# FPGA_IO.net
KiCad netlist of a schematic drawn in Altium Designer
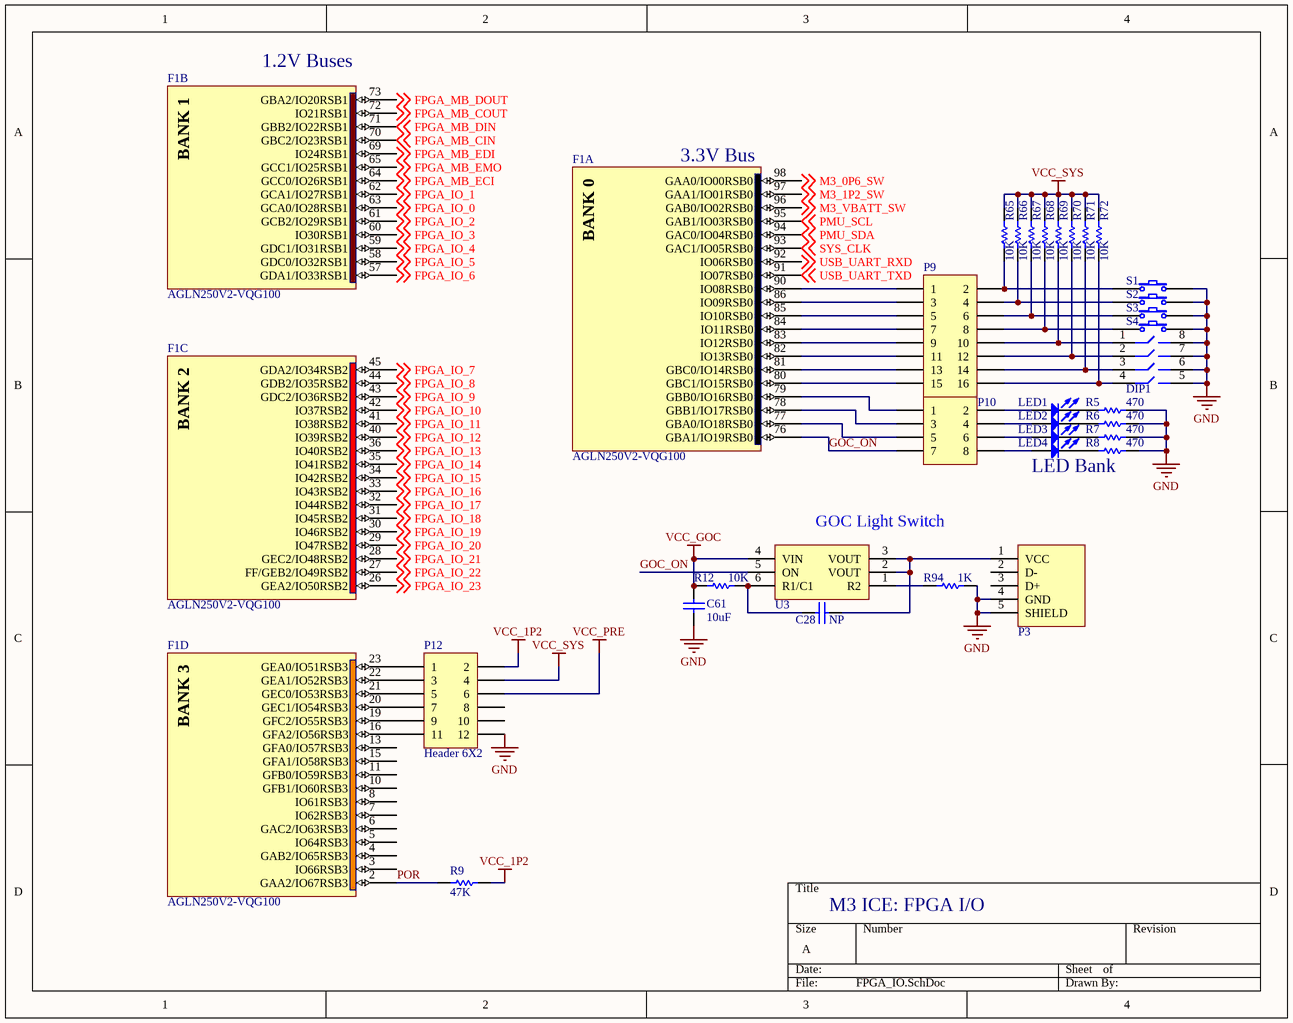
[diagram p0: FPGA_IO.SchDoc]

(export (version "E")
  (design (tool "Eeschema 10.0.6"))
  (components
    (comp (ref "C28")
      (value "NP")
      (footprint "0402")
      (description "Capacitor (Semiconductor SIM Model)")
      (fields (field (name "Comment") "Cap Semi") (field (name "PUBLISHER") "Altium Limited"))
      (libsource (lib "Miscellaneous Devices") (part "Cap Semi"))
    )
    (comp (ref "C61")
      (value "10uF")
      (footprint "0805")
      (description "Capacitor (Semiconductor SIM Model)")
      (fields
        (field (name "DISTPARTNO") "445-6857-1-ND")
        (field (name "MANPARTNO") "C2012X7R1A106K")
        (field (name "PUBLISHER") "Altium Limited")
      )
      (libsource (lib "M3") (part "Cap Chip"))
    )
    (comp (ref "DIP1")
      (value "ADE0404")
      (footprint "DIP-8")
      (description "4-DIP Switch")
      (fields (field (name "DISTPARTNO") "450-1364-ND"))
      (libsource (lib "M3") (part "ADE0404"))
    )
    (comp (ref "F1")
      (value "AGLN250V2-VQG100")
      (footprint "VQ100_N")
      (fields (field (name "DISTPARTNO") "1100-1134-ND") (field (name "PUBLISHER") "Altium Limited"))
      (libsource (lib "Actel IGLOO nano") (part "AGLN250V2-VQG100"))
    )
    (comp (ref "LED1")
      (value "LED 1206")
      (footprint "1206_LED")
      (fields (field (name "DISTPARTNO") "160-1169-1-ND") (field (name "MANPARTNO") "LTST-C150GKT"))
      (libsource (lib "M3") (part "LED 1206"))
    )
    (comp (ref "LED2")
      (value "LED 1206")
      (footprint "1206_LED")
      (fields (field (name "DISTPARTNO") "160-1169-1-ND") (field (name "MANPARTNO") "LTST-C150GKT"))
      (libsource (lib "M3") (part "LED 1206"))
    )
    (comp (ref "LED3")
      (value "LED 1206")
      (footprint "1206_LED")
      (fields (field (name "DISTPARTNO") "160-1169-1-ND") (field (name "MANPARTNO") "LTST-C150GKT"))
      (libsource (lib "M3") (part "LED 1206"))
    )
    (comp (ref "LED4")
      (value "LED 1206")
      (footprint "1206_LED")
      (fields (field (name "DISTPARTNO") "160-1169-1-ND") (field (name "MANPARTNO") "LTST-C150GKT"))
      (libsource (lib "M3") (part "LED 1206"))
    )
    (comp (ref "P3")
      (value "USB_HORIZONTAL")
      (footprint "USB_HORIZONTAL")
      (fields (field (name "DISTPARTNO") "A31726-ND") (field (name "MANPARTNO") "292303-1"))
      (libsource (lib "M3") (part "USB_HORIZONTAL"))
    )
    (comp (ref "P9")
      (value "Header 8X2")
      (footprint "HDR2X8")
      (description "Header, 8-Pin, Dual row")
      (fields
        (field (name "DISTPARTNO") "A26530-08-ND")
        (field (name "MANPARTNO") "4-103328-0-08")
        (field (name "PUBLISHER") "Altium Limited")
      )
      (libsource (lib "Miscellaneous Connectors") (part "Header 8X2"))
    )
    (comp (ref "P10")
      (value "Header 4X2")
      (footprint "HDR2X4")
      (description "Header, 4-Pin, Dual row")
      (fields
        (field (name "DISTPARTNO") "A26530-04-ND")
        (field (name "MANPARTNO") "4-103328-0-04")
        (field (name "PUBLISHER") "Altium Limited")
      )
      (libsource (lib "Miscellaneous Connectors") (part "Header 4X2"))
    )
    (comp (ref "P12")
      (value "Header 6X2")
      (footprint "HDR2X6")
      (description "Header, 6-Pin, Dual row")
      (fields
        (field (name "DISTPARTNO") "A26530-06-ND")
        (field (name "MANPARTNO") "4-103328-0-06")
        (field (name "PUBLISHER") "Altium Limited")
      )
      (libsource (lib "Miscellaneous Connectors") (part "Header 6X2"))
    )
    (comp (ref "R5")
      (value "470")
      (footprint "0603")
      (description "Semiconductor Resistor")
      (fields
        (field (name "DISTPARTNO") "P470GCT-ND")
        (field (name "MANPARTNO") "ERJ-3GEYJ471V")
        (field (name "PUBLISHER") "Altium Limited")
      )
      (libsource (lib "M3") (part "Res Chip"))
    )
    (comp (ref "R6")
      (value "470")
      (footprint "0603")
      (description "Semiconductor Resistor")
      (fields
        (field (name "DISTPARTNO") "P470GCT-ND")
        (field (name "MANPARTNO") "ERJ-3GEYJ471V")
        (field (name "PUBLISHER") "Altium Limited")
      )
      (libsource (lib "M3") (part "Res Chip"))
    )
    (comp (ref "R7")
      (value "470")
      (footprint "0603")
      (description "Semiconductor Resistor")
      (fields
        (field (name "DISTPARTNO") "P470GCT-ND")
        (field (name "MANPARTNO") "ERJ-3GEYJ471V")
        (field (name "PUBLISHER") "Altium Limited")
      )
      (libsource (lib "M3") (part "Res Chip"))
    )
    (comp (ref "R8")
      (value "470")
      (footprint "0603")
      (description "Semiconductor Resistor")
      (fields
        (field (name "DISTPARTNO") "P470GCT-ND")
        (field (name "MANPARTNO") "ERJ-3GEYJ471V")
        (field (name "PUBLISHER") "Altium Limited")
      )
      (libsource (lib "M3") (part "Res Chip"))
    )
    (comp (ref "R9")
      (value "47K")
      (footprint "0603")
      (description "Semiconductor Resistor")
      (fields
        (field (name "DISTPARTNO") "P47KGCT-ND")
        (field (name "MANPARTNO") "ERJ-3GEYJ103V")
        (field (name "PUBLISHER") "Altium Limited")
      )
      (libsource (lib "M3") (part "Res Chip"))
    )
    (comp (ref "R12")
      (value "10K")
      (footprint "0402")
      (description "Semiconductor Resistor")
      (fields
        (field (name "MANPARTNO") "ERJ-2RKF1002X")
        (field (name "DISTPARTNO") "P10.0KLCT-ND")
        (field (name "PUBLISHER") "Altium Limited")
      )
      (libsource (lib "M3") (part "Res Chip"))
    )
    (comp (ref "R65")
      (value "10K")
      (footprint "0603")
      (description "Semiconductor Resistor")
      (fields
        (field (name "DISTPARTNO") "P10KGCT-ND")
        (field (name "MANPARTNO") "ERJ-3GEYJ103V")
        (field (name "PUBLISHER") "Altium Limited")
      )
      (libsource (lib "M3") (part "Res Chip"))
    )
    (comp (ref "R66")
      (value "10K")
      (footprint "0603")
      (description "Semiconductor Resistor")
      (fields
        (field (name "DISTPARTNO") "P10KGCT-ND")
        (field (name "MANPARTNO") "ERJ-3GEYJ103V")
        (field (name "PUBLISHER") "Altium Limited")
      )
      (libsource (lib "M3") (part "Res Chip"))
    )
    (comp (ref "R67")
      (value "10K")
      (footprint "0603")
      (description "Semiconductor Resistor")
      (fields
        (field (name "DISTPARTNO") "P10KGCT-ND")
        (field (name "MANPARTNO") "ERJ-3GEYJ103V")
        (field (name "PUBLISHER") "Altium Limited")
      )
      (libsource (lib "M3") (part "Res Chip"))
    )
    (comp (ref "R68")
      (value "10K")
      (footprint "0603")
      (description "Semiconductor Resistor")
      (fields
        (field (name "DISTPARTNO") "P10KGCT-ND")
        (field (name "MANPARTNO") "ERJ-3GEYJ103V")
        (field (name "PUBLISHER") "Altium Limited")
      )
      (libsource (lib "M3") (part "Res Chip"))
    )
    (comp (ref "R69")
      (value "10K")
      (footprint "0603")
      (description "Semiconductor Resistor")
      (fields
        (field (name "DISTPARTNO") "P10KGCT-ND")
        (field (name "MANPARTNO") "ERJ-3GEYJ103V")
        (field (name "PUBLISHER") "Altium Limited")
      )
      (libsource (lib "M3") (part "Res Chip"))
    )
    (comp (ref "R70")
      (value "10K")
      (footprint "0603")
      (description "Semiconductor Resistor")
      (fields
        (field (name "DISTPARTNO") "P10KGCT-ND")
        (field (name "MANPARTNO") "ERJ-3GEYJ103V")
        (field (name "PUBLISHER") "Altium Limited")
      )
      (libsource (lib "M3") (part "Res Chip"))
    )
    (comp (ref "R71")
      (value "10K")
      (footprint "0603")
      (description "Semiconductor Resistor")
      (fields
        (field (name "DISTPARTNO") "P10KGCT-ND")
        (field (name "MANPARTNO") "ERJ-3GEYJ103V")
        (field (name "PUBLISHER") "Altium Limited")
      )
      (libsource (lib "M3") (part "Res Chip"))
    )
    (comp (ref "R72")
      (value "10K")
      (footprint "0603")
      (description "Semiconductor Resistor")
      (fields
        (field (name "DISTPARTNO") "P10KGCT-ND")
        (field (name "MANPARTNO") "ERJ-3GEYJ103V")
        (field (name "PUBLISHER") "Altium Limited")
      )
      (libsource (lib "M3") (part "Res Chip"))
    )
    (comp (ref "R94")
      (value "1K")
      (footprint "0402")
      (description "Semiconductor Resistor")
      (fields
        (field (name "MANPARTNO") "ERJ-2RKF1001X")
        (field (name "DISTPARTNO") "P1.00KLCT-ND")
        (field (name "PUBLISHER") "Altium Limited")
      )
      (libsource (lib "M3") (part "Res Chip"))
    )
    (comp (ref "S1")
      (value "EVQ-PAE04M")
      (footprint "EVQPA")
      (description "Switch Push")
      (fields (field (name "DISTPARTNO") "P8008S-ND"))
      (libsource (lib "M3") (part "EVQ-PAE04M"))
    )
    (comp (ref "S2")
      (value "EVQ-PAE04M")
      (footprint "EVQPA")
      (description "Switch Push")
      (fields (field (name "DISTPARTNO") "P8008S-ND"))
      (libsource (lib "M3") (part "EVQ-PAE04M"))
    )
    (comp (ref "S3")
      (value "EVQ-PAE04M")
      (footprint "EVQPA")
      (description "Switch Push")
      (fields (field (name "DISTPARTNO") "P8008S-ND"))
      (libsource (lib "M3") (part "EVQ-PAE04M"))
    )
    (comp (ref "S4")
      (value "EVQ-PAE04M")
      (footprint "EVQPA")
      (description "Switch Push")
      (fields (field (name "DISTPARTNO") "P8008S-ND"))
      (libsource (lib "M3") (part "EVQ-PAE04M"))
    )
    (comp (ref "U3")
      (value "FDC6330L")
      (footprint "SUPERSOT-6")
      (description "HS Switch")
      (fields (field (name "DISTPARTNO") "FDC6330LCT-ND"))
      (libsource (lib "M3") (part "FDC6330L"))
    )
  )
  (nets
    (net (code "1") (name "/GOC_ON") (class "Default")
      (node (ref "F1") (pin "76") (pinfunction "GBA1/IO19RSB0_76") (pintype "bidirectional"))
      (node (ref "P10") (pin "7") (pinfunction "7_7") (pintype "passive"))
      (node (ref "U3") (pin "5") (pinfunction "ON_5") (pintype "passive"))
    )
    (net (code "2") (name "/POR") (class "Default")
      (node (ref "F1") (pin "2") (pinfunction "GAA2/IO67RSB3_2") (pintype "bidirectional"))
      (node (ref "R9") (pin "1") (pinfunction "1_1") (pintype "passive"))
    )
    (net (code "3") (name "FPGA_IO_0") (class "Default")
      (node (ref "F1") (pin "63") (pinfunction "GCA0/IO28RSB1_63") (pintype "bidirectional"))
    )
    (net (code "4") (name "FPGA_IO_1") (class "Default")
      (node (ref "F1") (pin "62") (pinfunction "GCA1/IO27RSB1_62") (pintype "bidirectional"))
    )
    (net (code "5") (name "FPGA_IO_2") (class "Default")
      (node (ref "F1") (pin "61") (pinfunction "GCB2/IO29RSB1_61") (pintype "bidirectional"))
    )
    (net (code "6") (name "FPGA_IO_3") (class "Default")
      (node (ref "F1") (pin "60") (pinfunction "IO30RSB1_60") (pintype "bidirectional"))
    )
    (net (code "7") (name "FPGA_IO_4") (class "Default")
      (node (ref "F1") (pin "59") (pinfunction "GDC1/IO31RSB1_59") (pintype "bidirectional"))
    )
    (net (code "8") (name "FPGA_IO_5") (class "Default")
      (node (ref "F1") (pin "58") (pinfunction "GDC0/IO32RSB1_58") (pintype "bidirectional"))
    )
    (net (code "9") (name "FPGA_IO_6") (class "Default")
      (node (ref "F1") (pin "57") (pinfunction "GDA1/IO33RSB1_57") (pintype "bidirectional"))
    )
    (net (code "10") (name "FPGA_IO_7") (class "Default")
      (node (ref "F1") (pin "45") (pinfunction "GDA2/IO34RSB2_45") (pintype "bidirectional"))
    )
    (net (code "11") (name "FPGA_IO_8") (class "Default")
      (node (ref "F1") (pin "44") (pinfunction "GDB2/IO35RSB2_44") (pintype "bidirectional"))
    )
    (net (code "12") (name "FPGA_IO_9") (class "Default")
      (node (ref "F1") (pin "43") (pinfunction "GDC2/IO36RSB2_43") (pintype "bidirectional"))
    )
    (net (code "13") (name "FPGA_IO_10") (class "Default")
      (node (ref "F1") (pin "42") (pinfunction "IO37RSB2_42") (pintype "bidirectional"))
    )
    (net (code "14") (name "FPGA_IO_11") (class "Default")
      (node (ref "F1") (pin "41") (pinfunction "IO38RSB2_41") (pintype "bidirectional"))
    )
    (net (code "15") (name "FPGA_IO_12") (class "Default")
      (node (ref "F1") (pin "40") (pinfunction "IO39RSB2_40") (pintype "bidirectional"))
    )
    (net (code "16") (name "FPGA_IO_13") (class "Default")
      (node (ref "F1") (pin "36") (pinfunction "IO40RSB2_36") (pintype "bidirectional"))
    )
    (net (code "17") (name "FPGA_IO_14") (class "Default")
      (node (ref "F1") (pin "35") (pinfunction "IO41RSB2_35") (pintype "bidirectional"))
    )
    (net (code "18") (name "FPGA_IO_15") (class "Default")
      (node (ref "F1") (pin "34") (pinfunction "IO42RSB2_34") (pintype "bidirectional"))
    )
    (net (code "19") (name "FPGA_IO_16") (class "Default")
      (node (ref "F1") (pin "33") (pinfunction "IO43RSB2_33") (pintype "bidirectional"))
    )
    (net (code "20") (name "FPGA_IO_17") (class "Default")
      (node (ref "F1") (pin "32") (pinfunction "IO44RSB2_32") (pintype "bidirectional"))
    )
    (net (code "21") (name "FPGA_IO_18") (class "Default")
      (node (ref "F1") (pin "31") (pinfunction "IO45RSB2_31") (pintype "bidirectional"))
    )
    (net (code "22") (name "FPGA_IO_19") (class "Default")
      (node (ref "F1") (pin "30") (pinfunction "IO46RSB2_30") (pintype "bidirectional"))
    )
    (net (code "23") (name "FPGA_IO_20") (class "Default")
      (node (ref "F1") (pin "29") (pinfunction "IO47RSB2_29") (pintype "bidirectional"))
    )
    (net (code "24") (name "FPGA_IO_21") (class "Default")
      (node (ref "F1") (pin "28") (pinfunction "GEC2/IO48RSB2_28") (pintype "bidirectional"))
    )
    (net (code "25") (name "FPGA_IO_22") (class "Default")
      (node (ref "F1") (pin "27") (pinfunction "FF/GEB2/IO49RSB2_27") (pintype "bidirectional"))
    )
    (net (code "26") (name "FPGA_IO_23") (class "Default")
      (node (ref "F1") (pin "26") (pinfunction "GEA2/IO50RSB2_26") (pintype "bidirectional"))
    )
    (net (code "27") (name "FPGA_MB_CIN") (class "Default")
      (node (ref "F1") (pin "70") (pinfunction "GBC2/IO23RSB1_70") (pintype "bidirectional"))
    )
    (net (code "28") (name "FPGA_MB_COUT") (class "Default")
      (node (ref "F1") (pin "72") (pinfunction "IO21RSB1_72") (pintype "bidirectional"))
    )
    (net (code "29") (name "FPGA_MB_DIN") (class "Default")
      (node (ref "F1") (pin "71") (pinfunction "GBB2/IO22RSB1_71") (pintype "bidirectional"))
    )
    (net (code "30") (name "FPGA_MB_DOUT") (class "Default")
      (node (ref "F1") (pin "73") (pinfunction "GBA2/IO20RSB1_73") (pintype "bidirectional"))
    )
    (net (code "31") (name "FPGA_MB_ECI") (class "Default")
      (node (ref "F1") (pin "64") (pinfunction "GCC0/IO26RSB1_64") (pintype "bidirectional"))
    )
    (net (code "32") (name "FPGA_MB_EDI") (class "Default")
      (node (ref "F1") (pin "69") (pinfunction "IO24RSB1_69") (pintype "bidirectional"))
    )
    (net (code "33") (name "FPGA_MB_EMO") (class "Default")
      (node (ref "F1") (pin "65") (pinfunction "GCC1/IO25RSB1_65") (pintype "bidirectional"))
    )
    (net (code "34") (name "GND") (class "Default")
      (node (ref "C61") (pin "2") (pinfunction "2_2") (pintype "passive"))
      (node (ref "DIP1") (pin "5") (pinfunction "5_5") (pintype "passive"))
      (node (ref "DIP1") (pin "6") (pinfunction "6_6") (pintype "passive"))
      (node (ref "DIP1") (pin "7") (pinfunction "7_7") (pintype "passive"))
      (node (ref "DIP1") (pin "8") (pinfunction "8_8") (pintype "passive"))
      (node (ref "P12") (pin "12") (pinfunction "12_12") (pintype "passive"))
      (node (ref "P3") (pin "4") (pinfunction "GND_4") (pintype "passive"))
      (node (ref "P3") (pin "5") (pinfunction "SHIELD_5") (pintype "passive"))
      (node (ref "R5") (pin "1") (pinfunction "1_1") (pintype "passive"))
      (node (ref "R6") (pin "1") (pinfunction "1_1") (pintype "passive"))
      (node (ref "R7") (pin "1") (pinfunction "1_1") (pintype "passive"))
      (node (ref "R8") (pin "1") (pinfunction "1_1") (pintype "passive"))
      (node (ref "R94") (pin "2") (pinfunction "2_2") (pintype "passive"))
      (node (ref "S1") (pin "2") (pinfunction "2_2") (pintype "passive"))
      (node (ref "S2") (pin "2") (pinfunction "2_2") (pintype "passive"))
      (node (ref "S3") (pin "2") (pinfunction "2_2") (pintype "passive"))
      (node (ref "S4") (pin "2") (pinfunction "2_2") (pintype "passive"))
    )
    (net (code "35") (name "M3_0P6_SW") (class "Default")
      (node (ref "F1") (pin "98") (pinfunction "GAA0/IO00RSB0_98") (pintype "bidirectional"))
    )
    (net (code "36") (name "M3_1P2_SW") (class "Default")
      (node (ref "F1") (pin "97") (pinfunction "GAA1/IO01RSB0_97") (pintype "bidirectional"))
    )
    (net (code "37") (name "M3_VBATT_SW") (class "Default")
      (node (ref "F1") (pin "96") (pinfunction "GAB0/IO02RSB0_96") (pintype "bidirectional"))
    )
    (net (code "38") (name "Net-(DIP1-Pad1)") (class "Default")
      (node (ref "DIP1") (pin "1") (pinfunction "1_1") (pintype "passive"))
      (node (ref "P9") (pin "10") (pinfunction "10_10") (pintype "passive"))
      (node (ref "R69") (pin "2") (pinfunction "2_2") (pintype "passive"))
    )
    (net (code "39") (name "Net-(DIP1-Pad2)") (class "Default")
      (node (ref "DIP1") (pin "2") (pinfunction "2_2") (pintype "passive"))
      (node (ref "P9") (pin "12") (pinfunction "12_12") (pintype "passive"))
      (node (ref "R70") (pin "2") (pinfunction "2_2") (pintype "passive"))
    )
    (net (code "40") (name "Net-(DIP1-Pad3)") (class "Default")
      (node (ref "DIP1") (pin "3") (pinfunction "3_3") (pintype "passive"))
      (node (ref "P9") (pin "14") (pinfunction "14_14") (pintype "passive"))
      (node (ref "R71") (pin "2") (pinfunction "2_2") (pintype "passive"))
    )
    (net (code "41") (name "Net-(DIP1-Pad4)") (class "Default")
      (node (ref "DIP1") (pin "4") (pinfunction "4_4") (pintype "passive"))
      (node (ref "P9") (pin "16") (pinfunction "16_16") (pintype "passive"))
      (node (ref "R72") (pin "2") (pinfunction "2_2") (pintype "passive"))
    )
    (net (code "42") (name "Net-(F1A-GBA0{slash}IO18RSB0)") (class "Default")
      (node (ref "F1") (pin "77") (pinfunction "GBA0/IO18RSB0_77") (pintype "bidirectional"))
      (node (ref "P10") (pin "5") (pinfunction "5_5") (pintype "passive"))
    )
    (net (code "43") (name "Net-(F1A-GBB0{slash}IO16RSB0)") (class "Default")
      (node (ref "F1") (pin "79") (pinfunction "GBB0/IO16RSB0_79") (pintype "bidirectional"))
      (node (ref "P10") (pin "1") (pinfunction "1_1") (pintype "passive"))
    )
    (net (code "44") (name "Net-(F1A-GBB1{slash}IO17RSB0)") (class "Default")
      (node (ref "F1") (pin "78") (pinfunction "GBB1/IO17RSB0_78") (pintype "bidirectional"))
      (node (ref "P10") (pin "3") (pinfunction "3_3") (pintype "passive"))
    )
    (net (code "45") (name "Net-(F1A-GBC0{slash}IO14RSB0)") (class "Default")
      (node (ref "F1") (pin "81") (pinfunction "GBC0/IO14RSB0_81") (pintype "bidirectional"))
      (node (ref "P9") (pin "13") (pinfunction "13_13") (pintype "passive"))
    )
    (net (code "46") (name "Net-(F1A-GBC1{slash}IO15RSB0)") (class "Default")
      (node (ref "F1") (pin "80") (pinfunction "GBC1/IO15RSB0_80") (pintype "bidirectional"))
      (node (ref "P9") (pin "15") (pinfunction "15_15") (pintype "passive"))
    )
    (net (code "47") (name "Net-(F1A-IO08RSB0)") (class "Default")
      (node (ref "F1") (pin "90") (pinfunction "IO08RSB0_90") (pintype "bidirectional"))
      (node (ref "P9") (pin "1") (pinfunction "1_1") (pintype "passive"))
    )
    (net (code "48") (name "Net-(F1A-IO09RSB0)") (class "Default")
      (node (ref "F1") (pin "86") (pinfunction "IO09RSB0_86") (pintype "bidirectional"))
      (node (ref "P9") (pin "3") (pinfunction "3_3") (pintype "passive"))
    )
    (net (code "49") (name "Net-(F1A-IO10RSB0)") (class "Default")
      (node (ref "F1") (pin "85") (pinfunction "IO10RSB0_85") (pintype "bidirectional"))
      (node (ref "P9") (pin "5") (pinfunction "5_5") (pintype "passive"))
    )
    (net (code "50") (name "Net-(F1A-IO11RSB0)") (class "Default")
      (node (ref "F1") (pin "84") (pinfunction "IO11RSB0_84") (pintype "bidirectional"))
      (node (ref "P9") (pin "7") (pinfunction "7_7") (pintype "passive"))
    )
    (net (code "51") (name "Net-(F1A-IO12RSB0)") (class "Default")
      (node (ref "F1") (pin "83") (pinfunction "IO12RSB0_83") (pintype "bidirectional"))
      (node (ref "P9") (pin "9") (pinfunction "9_9") (pintype "passive"))
    )
    (net (code "52") (name "Net-(F1A-IO13RSB0)") (class "Default")
      (node (ref "F1") (pin "82") (pinfunction "IO13RSB0_82") (pintype "bidirectional"))
      (node (ref "P9") (pin "11") (pinfunction "11_11") (pintype "passive"))
    )
    (net (code "53") (name "Net-(F1D-GEA0{slash}IO51RSB3)") (class "Default")
      (node (ref "F1") (pin "23") (pinfunction "GEA0/IO51RSB3_23") (pintype "bidirectional"))
      (node (ref "P12") (pin "1") (pinfunction "1_1") (pintype "passive"))
    )
    (net (code "54") (name "Net-(F1D-GEA1{slash}IO52RSB3)") (class "Default")
      (node (ref "F1") (pin "22") (pinfunction "GEA1/IO52RSB3_22") (pintype "bidirectional"))
      (node (ref "P12") (pin "3") (pinfunction "3_3") (pintype "passive"))
    )
    (net (code "55") (name "Net-(F1D-GEC0{slash}IO53RSB3)") (class "Default")
      (node (ref "F1") (pin "21") (pinfunction "GEC0/IO53RSB3_21") (pintype "bidirectional"))
      (node (ref "P12") (pin "5") (pinfunction "5_5") (pintype "passive"))
    )
    (net (code "56") (name "Net-(F1D-GEC1{slash}IO54RSB3)") (class "Default")
      (node (ref "F1") (pin "20") (pinfunction "GEC1/IO54RSB3_20") (pintype "bidirectional"))
      (node (ref "P12") (pin "7") (pinfunction "7_7") (pintype "passive"))
    )
    (net (code "57") (name "Net-(F1D-GFA2{slash}IO56RSB3)") (class "Default")
      (node (ref "F1") (pin "16") (pinfunction "GFA2/IO56RSB3_16") (pintype "bidirectional"))
      (node (ref "P12") (pin "11") (pinfunction "11_11") (pintype "passive"))
    )
    (net (code "58") (name "Net-(F1D-GFC2{slash}IO55RSB3)") (class "Default")
      (node (ref "F1") (pin "19") (pinfunction "GFC2/IO55RSB3_19") (pintype "bidirectional"))
      (node (ref "P12") (pin "9") (pinfunction "9_9") (pintype "passive"))
    )
    (net (code "59") (name "Net-(LED1-A)") (class "Default")
      (node (ref "LED1") (pin "1") (pinfunction "A_1") (pintype "passive"))
      (node (ref "P10") (pin "2") (pinfunction "2_2") (pintype "passive"))
    )
    (net (code "60") (name "Net-(LED1-K)") (class "Default")
      (node (ref "LED1") (pin "2") (pinfunction "K_2") (pintype "passive"))
      (node (ref "R5") (pin "2") (pinfunction "2_2") (pintype "passive"))
    )
    (net (code "61") (name "Net-(LED2-A)") (class "Default")
      (node (ref "LED2") (pin "1") (pinfunction "A_1") (pintype "passive"))
      (node (ref "P10") (pin "4") (pinfunction "4_4") (pintype "passive"))
    )
    (net (code "62") (name "Net-(LED2-K)") (class "Default")
      (node (ref "LED2") (pin "2") (pinfunction "K_2") (pintype "passive"))
      (node (ref "R6") (pin "2") (pinfunction "2_2") (pintype "passive"))
    )
    (net (code "63") (name "Net-(LED3-A)") (class "Default")
      (node (ref "LED3") (pin "1") (pinfunction "A_1") (pintype "passive"))
      (node (ref "P10") (pin "6") (pinfunction "6_6") (pintype "passive"))
    )
    (net (code "64") (name "Net-(LED3-K)") (class "Default")
      (node (ref "LED3") (pin "2") (pinfunction "K_2") (pintype "passive"))
      (node (ref "R7") (pin "2") (pinfunction "2_2") (pintype "passive"))
    )
    (net (code "65") (name "Net-(LED4-A)") (class "Default")
      (node (ref "LED4") (pin "1") (pinfunction "A_1") (pintype "passive"))
      (node (ref "P10") (pin "8") (pinfunction "8_8") (pintype "passive"))
    )
    (net (code "66") (name "Net-(LED4-K)") (class "Default")
      (node (ref "LED4") (pin "2") (pinfunction "K_2") (pintype "passive"))
      (node (ref "R8") (pin "2") (pinfunction "2_2") (pintype "passive"))
    )
    (net (code "67") (name "Net-(P3-VCC)") (class "Default")
      (node (ref "C28") (pin "1") (pinfunction "1_1") (pintype "passive"))
      (node (ref "P3") (pin "1") (pinfunction "VCC_1") (pintype "passive"))
      (node (ref "U3") (pin "2") (pinfunction "VOUT_2") (pintype "passive"))
      (node (ref "U3") (pin "3") (pinfunction "VOUT_3") (pintype "passive"))
    )
    (net (code "68") (name "Net-(P9-Pad2)") (class "Default")
      (node (ref "P9") (pin "2") (pinfunction "2_2") (pintype "passive"))
      (node (ref "R65") (pin "2") (pinfunction "2_2") (pintype "passive"))
      (node (ref "S1") (pin "1") (pinfunction "1_1") (pintype "passive"))
    )
    (net (code "69") (name "Net-(P9-Pad4)") (class "Default")
      (node (ref "P9") (pin "4") (pinfunction "4_4") (pintype "passive"))
      (node (ref "R66") (pin "2") (pinfunction "2_2") (pintype "passive"))
      (node (ref "S2") (pin "1") (pinfunction "1_1") (pintype "passive"))
    )
    (net (code "70") (name "Net-(P9-Pad6)") (class "Default")
      (node (ref "P9") (pin "6") (pinfunction "6_6") (pintype "passive"))
      (node (ref "R67") (pin "2") (pinfunction "2_2") (pintype "passive"))
      (node (ref "S3") (pin "1") (pinfunction "1_1") (pintype "passive"))
    )
    (net (code "71") (name "Net-(P9-Pad8)") (class "Default")
      (node (ref "P9") (pin "8") (pinfunction "8_8") (pintype "passive"))
      (node (ref "R68") (pin "2") (pinfunction "2_2") (pintype "passive"))
      (node (ref "S4") (pin "1") (pinfunction "1_1") (pintype "passive"))
    )
    (net (code "72") (name "Net-(U3-R1{slash}C1)") (class "Default")
      (node (ref "C28") (pin "2") (pinfunction "2_2") (pintype "passive"))
      (node (ref "R12") (pin "2") (pinfunction "2_2") (pintype "passive"))
      (node (ref "U3") (pin "6") (pinfunction "R1/C1_6") (pintype "passive"))
    )
    (net (code "73") (name "Net-(U3-R2)") (class "Default")
      (node (ref "R94") (pin "1") (pinfunction "1_1") (pintype "passive"))
      (node (ref "U3") (pin "1") (pinfunction "R2_1") (pintype "passive"))
    )
    (net (code "74") (name "PMU_SCL") (class "Default")
      (node (ref "F1") (pin "95") (pinfunction "GAB1/IO03RSB0_95") (pintype "bidirectional"))
    )
    (net (code "75") (name "PMU_SDA") (class "Default")
      (node (ref "F1") (pin "94") (pinfunction "GAC0/IO04RSB0_94") (pintype "bidirectional"))
    )
    (net (code "76") (name "SYS_CLK") (class "Default")
      (node (ref "F1") (pin "93") (pinfunction "GAC1/IO05RSB0_93") (pintype "bidirectional"))
    )
    (net (code "77") (name "USB_UART_RXD") (class "Default")
      (node (ref "F1") (pin "92") (pinfunction "IO06RSB0_92") (pintype "bidirectional"))
    )
    (net (code "78") (name "USB_UART_TXD") (class "Default")
      (node (ref "F1") (pin "91") (pinfunction "IO07RSB0_91") (pintype "bidirectional"))
    )
    (net (code "79") (name "VCC_1P2") (class "Default")
      (node (ref "P12") (pin "2") (pinfunction "2_2") (pintype "passive"))
      (node (ref "R9") (pin "2") (pinfunction "2_2") (pintype "passive"))
    )
    (net (code "80") (name "VCC_GOC") (class "Default")
      (node (ref "C61") (pin "1") (pinfunction "1_1") (pintype "passive"))
      (node (ref "R12") (pin "1") (pinfunction "1_1") (pintype "passive"))
      (node (ref "U3") (pin "4") (pinfunction "VIN_4") (pintype "passive"))
    )
    (net (code "81") (name "VCC_PRE") (class "Default")
      (node (ref "P12") (pin "6") (pinfunction "6_6") (pintype "passive"))
    )
    (net (code "82") (name "VCC_SYS") (class "Default")
      (node (ref "P12") (pin "4") (pinfunction "4_4") (pintype "passive"))
      (node (ref "R65") (pin "1") (pinfunction "1_1") (pintype "passive"))
      (node (ref "R66") (pin "1") (pinfunction "1_1") (pintype "passive"))
      (node (ref "R67") (pin "1") (pinfunction "1_1") (pintype "passive"))
      (node (ref "R68") (pin "1") (pinfunction "1_1") (pintype "passive"))
      (node (ref "R69") (pin "1") (pinfunction "1_1") (pintype "passive"))
      (node (ref "R70") (pin "1") (pinfunction "1_1") (pintype "passive"))
      (node (ref "R71") (pin "1") (pinfunction "1_1") (pintype "passive"))
      (node (ref "R72") (pin "1") (pinfunction "1_1") (pintype "passive"))
    )
    (net (code "83") (name "unconnected-(F1D-GAB2{slash}IO65RSB3-Pad4)") (class "Default")
      (node (ref "F1") (pin "4") (pinfunction "GAB2/IO65RSB3_4") (pintype "bidirectional"))
    )
    (net (code "84") (name "unconnected-(F1D-GAC2{slash}IO63RSB3-Pad6)") (class "Default")
      (node (ref "F1") (pin "6") (pinfunction "GAC2/IO63RSB3_6") (pintype "bidirectional"))
    )
    (net (code "85") (name "unconnected-(F1D-GFA0{slash}IO57RSB3-Pad13)") (class "Default")
      (node (ref "F1") (pin "13") (pinfunction "GFA0/IO57RSB3_13") (pintype "bidirectional"))
    )
    (net (code "86") (name "unconnected-(F1D-GFA1{slash}IO58RSB3-Pad15)") (class "Default")
      (node (ref "F1") (pin "15") (pinfunction "GFA1/IO58RSB3_15") (pintype "bidirectional"))
    )
    (net (code "87") (name "unconnected-(F1D-GFB0{slash}IO59RSB3-Pad11)") (class "Default")
      (node (ref "F1") (pin "11") (pinfunction "GFB0/IO59RSB3_11") (pintype "bidirectional"))
    )
    (net (code "88") (name "unconnected-(F1D-GFB1{slash}IO60RSB3-Pad10)") (class "Default")
      (node (ref "F1") (pin "10") (pinfunction "GFB1/IO60RSB3_10") (pintype "bidirectional"))
    )
    (net (code "89") (name "unconnected-(F1D-IO61RSB3-Pad8)") (class "Default")
      (node (ref "F1") (pin "8") (pinfunction "IO61RSB3_8") (pintype "bidirectional"))
    )
    (net (code "90") (name "unconnected-(F1D-IO62RSB3-Pad7)") (class "Default")
      (node (ref "F1") (pin "7") (pinfunction "IO62RSB3_7") (pintype "bidirectional"))
    )
    (net (code "91") (name "unconnected-(F1D-IO64RSB3-Pad5)") (class "Default")
      (node (ref "F1") (pin "5") (pinfunction "IO64RSB3_5") (pintype "bidirectional"))
    )
    (net (code "92") (name "unconnected-(F1D-IO66RSB3-Pad3)") (class "Default")
      (node (ref "F1") (pin "3") (pinfunction "IO66RSB3_3") (pintype "bidirectional"))
    )
    (net (code "93") (name "unconnected-(P3-D+-Pad3)") (class "Default")
      (node (ref "P3") (pin "3") (pinfunction "D+_3") (pintype "passive"))
    )
    (net (code "94") (name "unconnected-(P3-D--Pad2)") (class "Default")
      (node (ref "P3") (pin "2") (pinfunction "D-_2") (pintype "passive"))
    )
    (net (code "95") (name "unconnected-(P12-Pad8)") (class "Default")
      (node (ref "P12") (pin "8") (pinfunction "8_8") (pintype "passive"))
    )
    (net (code "96") (name "unconnected-(P12-Pad10)") (class "Default")
      (node (ref "P12") (pin "10") (pinfunction "10_10") (pintype "passive"))
    )
  )
)
